# Sheet1.net
KiCad netlist of a schematic drawn in Altium Designer
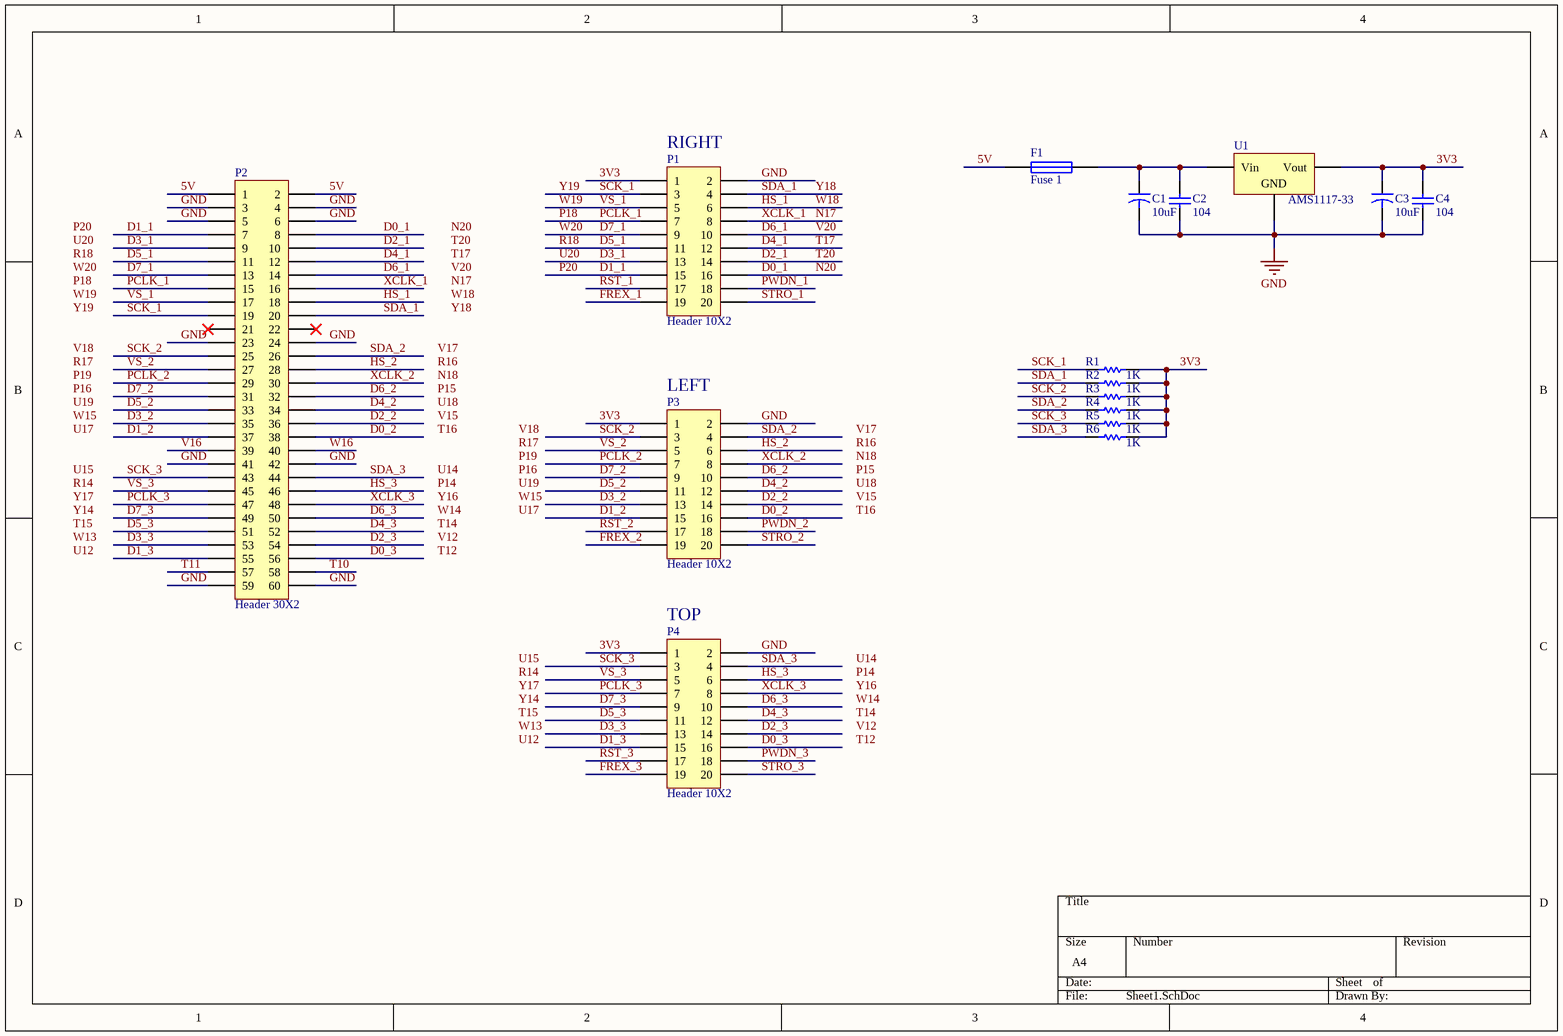
[diagram p0: Sheet1.SchDoc]

(export (version "E")
  (design (tool "Eeschema 10.0.6"))
  (components
    (comp (ref "C1")
      (value "10uF")
      (footprint "R0805")
      (description "Capacitor")
      (fields (field (name "Comment") "Cap2") (field (name "PUBLISHER") "Altium Limited"))
      (libsource (lib "Miscellaneous Devices") (part "Cap2"))
    )
    (comp (ref "C2")
      (value "104")
      (footprint "R0805")
      (description "Capacitor")
      (fields (field (name "Comment") "Cap") (field (name "PUBLISHER") "Altium Limited"))
      (libsource (lib "Miscellaneous Devices") (part "Cap"))
    )
    (comp (ref "C3")
      (value "10uF")
      (footprint "R0805")
      (description "Capacitor")
      (fields (field (name "Comment") "Cap2") (field (name "PUBLISHER") "Altium Limited"))
      (libsource (lib "Miscellaneous Devices") (part "Cap2"))
    )
    (comp (ref "C4")
      (value "104")
      (footprint "R0805")
      (description "Capacitor")
      (fields (field (name "Comment") "Cap") (field (name "PUBLISHER") "Altium Limited"))
      (libsource (lib "Miscellaneous Devices") (part "Cap"))
    )
    (comp (ref "F1")
      (value "Fuse 1")
      (footprint "R1206")
      (description "Fuse")
      (fields (field (name "PUBLISHER") "Altium Limited"))
      (libsource (lib "Miscellaneous Devices") (part "Fuse 1"))
    )
    (comp (ref "P1")
      (value "Header 10X2")
      (footprint "PCBComponent_1")
      (description "Header, 10-Pin, Dual row")
      (fields (field (name "PUBLISHER") "Altium Limited"))
      (libsource (lib "Miscellaneous Connectors") (part "Header 10X2"))
    )
    (comp (ref "P2")
      (value "Header 30X2")
      (footprint "BTBCON_0.8mm_60P")
      (description "Header, 30-Pin, Dual row")
      (fields (field (name "PUBLISHER") "Altium Limited"))
      (libsource (lib "Miscellaneous Connectors") (part "Header 30X2"))
    )
    (comp (ref "P3")
      (value "Header 10X2")
      (footprint "PCBComponent_1")
      (description "Header, 10-Pin, Dual row")
      (fields (field (name "PUBLISHER") "Altium Limited"))
      (libsource (lib "Miscellaneous Connectors") (part "Header 10X2"))
    )
    (comp (ref "P4")
      (value "Header 10X2")
      (footprint "PCBComponent_1")
      (description "Header, 10-Pin, Dual row")
      (fields (field (name "PUBLISHER") "Altium Limited"))
      (libsource (lib "Miscellaneous Connectors") (part "Header 10X2"))
    )
    (comp (ref "R1")
      (value "1K")
      (footprint "R0805")
      (description "Resistor")
      (fields (field (name "Comment") "Res1") (field (name "PUBLISHER") "Altium Limited"))
      (libsource (lib "Miscellaneous Devices") (part "Res1"))
    )
    (comp (ref "R2")
      (value "1K")
      (footprint "R0805")
      (description "Resistor")
      (fields (field (name "Comment") "Res1") (field (name "PUBLISHER") "Altium Limited"))
      (libsource (lib "Miscellaneous Devices") (part "Res1"))
    )
    (comp (ref "R3")
      (value "1K")
      (footprint "R0805")
      (description "Resistor")
      (fields (field (name "Comment") "Res1") (field (name "PUBLISHER") "Altium Limited"))
      (libsource (lib "Miscellaneous Devices") (part "Res1"))
    )
    (comp (ref "R4")
      (value "1K")
      (footprint "R0805")
      (description "Resistor")
      (fields (field (name "Comment") "Res1") (field (name "PUBLISHER") "Altium Limited"))
      (libsource (lib "Miscellaneous Devices") (part "Res1"))
    )
    (comp (ref "R5")
      (value "1K")
      (footprint "R0805")
      (description "Resistor")
      (fields (field (name "Comment") "Res1") (field (name "PUBLISHER") "Altium Limited"))
      (libsource (lib "Miscellaneous Devices") (part "Res1"))
    )
    (comp (ref "R6")
      (value "1K")
      (footprint "R0805")
      (description "Resistor")
      (fields (field (name "Comment") "Res1") (field (name "PUBLISHER") "Altium Limited"))
      (libsource (lib "Miscellaneous Devices") (part "Res1"))
    )
    (comp (ref "U1")
      (value "AMS1117-33")
      (footprint "SOT-223   AMS1117")
      (description "Voltage Regulator")
      (fields (field (name "PUBLISHER") "Altium Limited"))
      (libsource (lib "Miscellaneous Devices") (part "Volt Reg"))
    )
  )
  (nets
    (net (code "1") (name "/3V3") (class "Default")
      (node (ref "C3") (pin "1") (pinfunction "1_1") (pintype "passive"))
      (node (ref "C4") (pin "2") (pinfunction "2_2") (pintype "passive"))
      (node (ref "P1") (pin "1") (pinfunction "1_1") (pintype "passive"))
      (node (ref "P3") (pin "1") (pinfunction "1_1") (pintype "passive"))
      (node (ref "P4") (pin "1") (pinfunction "1_1") (pintype "passive"))
      (node (ref "R1") (pin "1") (pinfunction "1_1") (pintype "passive"))
      (node (ref "R2") (pin "1") (pinfunction "1_1") (pintype "passive"))
      (node (ref "R3") (pin "1") (pinfunction "1_1") (pintype "passive"))
      (node (ref "R4") (pin "1") (pinfunction "1_1") (pintype "passive"))
      (node (ref "R5") (pin "1") (pinfunction "1_1") (pintype "passive"))
      (node (ref "R6") (pin "1") (pinfunction "1_1") (pintype "passive"))
      (node (ref "U1") (pin "2") (pinfunction "Vout_2") (pintype "passive"))
    )
    (net (code "2") (name "/5V") (class "Default")
      (node (ref "F1") (pin "1") (pinfunction "1_1") (pintype "passive"))
      (node (ref "P2") (pin "1") (pinfunction "1_1") (pintype "passive"))
      (node (ref "P2") (pin "2") (pinfunction "2_2") (pintype "passive"))
    )
    (net (code "3") (name "/D0_1") (class "Default")
      (node (ref "P1") (pin "16") (pinfunction "16_16") (pintype "passive"))
      (node (ref "P2") (pin "8") (pinfunction "8_8") (pintype "passive"))
    )
    (net (code "4") (name "/D0_2") (class "Default")
      (node (ref "P2") (pin "38") (pinfunction "38_38") (pintype "passive"))
      (node (ref "P3") (pin "16") (pinfunction "16_16") (pintype "passive"))
    )
    (net (code "5") (name "/D0_3") (class "Default")
      (node (ref "P2") (pin "56") (pinfunction "56_56") (pintype "passive"))
      (node (ref "P4") (pin "16") (pinfunction "16_16") (pintype "passive"))
    )
    (net (code "6") (name "/D1_1") (class "Default")
      (node (ref "P1") (pin "15") (pinfunction "15_15") (pintype "passive"))
      (node (ref "P2") (pin "7") (pinfunction "7_7") (pintype "passive"))
    )
    (net (code "7") (name "/D1_2") (class "Default")
      (node (ref "P2") (pin "37") (pinfunction "37_37") (pintype "passive"))
      (node (ref "P3") (pin "15") (pinfunction "15_15") (pintype "passive"))
    )
    (net (code "8") (name "/D1_3") (class "Default")
      (node (ref "P2") (pin "55") (pinfunction "55_55") (pintype "passive"))
      (node (ref "P4") (pin "15") (pinfunction "15_15") (pintype "passive"))
    )
    (net (code "9") (name "/D2_1") (class "Default")
      (node (ref "P1") (pin "14") (pinfunction "14_14") (pintype "passive"))
      (node (ref "P2") (pin "10") (pinfunction "10_10") (pintype "passive"))
    )
    (net (code "10") (name "/D2_2") (class "Default")
      (node (ref "P2") (pin "36") (pinfunction "36_36") (pintype "passive"))
      (node (ref "P3") (pin "14") (pinfunction "14_14") (pintype "passive"))
    )
    (net (code "11") (name "/D2_3") (class "Default")
      (node (ref "P2") (pin "54") (pinfunction "54_54") (pintype "passive"))
      (node (ref "P4") (pin "14") (pinfunction "14_14") (pintype "passive"))
    )
    (net (code "12") (name "/D3_1") (class "Default")
      (node (ref "P1") (pin "13") (pinfunction "13_13") (pintype "passive"))
      (node (ref "P2") (pin "9") (pinfunction "9_9") (pintype "passive"))
    )
    (net (code "13") (name "/D3_2") (class "Default")
      (node (ref "P2") (pin "35") (pinfunction "35_35") (pintype "passive"))
      (node (ref "P3") (pin "13") (pinfunction "13_13") (pintype "passive"))
    )
    (net (code "14") (name "/D3_3") (class "Default")
      (node (ref "P2") (pin "53") (pinfunction "53_53") (pintype "passive"))
      (node (ref "P4") (pin "13") (pinfunction "13_13") (pintype "passive"))
    )
    (net (code "15") (name "/D4_1") (class "Default")
      (node (ref "P1") (pin "12") (pinfunction "12_12") (pintype "passive"))
      (node (ref "P2") (pin "12") (pinfunction "12_12") (pintype "passive"))
    )
    (net (code "16") (name "/D4_2") (class "Default")
      (node (ref "P2") (pin "34") (pinfunction "34_34") (pintype "passive"))
      (node (ref "P3") (pin "12") (pinfunction "12_12") (pintype "passive"))
    )
    (net (code "17") (name "/D4_3") (class "Default")
      (node (ref "P2") (pin "52") (pinfunction "52_52") (pintype "passive"))
      (node (ref "P4") (pin "12") (pinfunction "12_12") (pintype "passive"))
    )
    (net (code "18") (name "/D5_1") (class "Default")
      (node (ref "P1") (pin "11") (pinfunction "11_11") (pintype "passive"))
      (node (ref "P2") (pin "11") (pinfunction "11_11") (pintype "passive"))
    )
    (net (code "19") (name "/D5_2") (class "Default")
      (node (ref "P2") (pin "33") (pinfunction "33_33") (pintype "passive"))
      (node (ref "P3") (pin "11") (pinfunction "11_11") (pintype "passive"))
    )
    (net (code "20") (name "/D5_3") (class "Default")
      (node (ref "P2") (pin "51") (pinfunction "51_51") (pintype "passive"))
      (node (ref "P4") (pin "11") (pinfunction "11_11") (pintype "passive"))
    )
    (net (code "21") (name "/D6_1") (class "Default")
      (node (ref "P1") (pin "10") (pinfunction "10_10") (pintype "passive"))
      (node (ref "P2") (pin "14") (pinfunction "14_14") (pintype "passive"))
    )
    (net (code "22") (name "/D6_2") (class "Default")
      (node (ref "P2") (pin "32") (pinfunction "32_32") (pintype "passive"))
      (node (ref "P3") (pin "10") (pinfunction "10_10") (pintype "passive"))
    )
    (net (code "23") (name "/D6_3") (class "Default")
      (node (ref "P2") (pin "50") (pinfunction "50_50") (pintype "passive"))
      (node (ref "P4") (pin "10") (pinfunction "10_10") (pintype "passive"))
    )
    (net (code "24") (name "/D7_1") (class "Default")
      (node (ref "P1") (pin "9") (pinfunction "9_9") (pintype "passive"))
      (node (ref "P2") (pin "13") (pinfunction "13_13") (pintype "passive"))
    )
    (net (code "25") (name "/D7_2") (class "Default")
      (node (ref "P2") (pin "31") (pinfunction "31_31") (pintype "passive"))
      (node (ref "P3") (pin "9") (pinfunction "9_9") (pintype "passive"))
    )
    (net (code "26") (name "/D7_3") (class "Default")
      (node (ref "P2") (pin "49") (pinfunction "49_49") (pintype "passive"))
      (node (ref "P4") (pin "9") (pinfunction "9_9") (pintype "passive"))
    )
    (net (code "27") (name "/FREX_1") (class "Default")
      (node (ref "P1") (pin "19") (pinfunction "19_19") (pintype "passive"))
    )
    (net (code "28") (name "/FREX_2") (class "Default")
      (node (ref "P3") (pin "19") (pinfunction "19_19") (pintype "passive"))
    )
    (net (code "29") (name "/FREX_3") (class "Default")
      (node (ref "P4") (pin "19") (pinfunction "19_19") (pintype "passive"))
    )
    (net (code "30") (name "/HS_1") (class "Default")
      (node (ref "P1") (pin "6") (pinfunction "6_6") (pintype "passive"))
      (node (ref "P2") (pin "18") (pinfunction "18_18") (pintype "passive"))
    )
    (net (code "31") (name "/HS_2") (class "Default")
      (node (ref "P2") (pin "28") (pinfunction "28_28") (pintype "passive"))
      (node (ref "P3") (pin "6") (pinfunction "6_6") (pintype "passive"))
    )
    (net (code "32") (name "/HS_3") (class "Default")
      (node (ref "P2") (pin "46") (pinfunction "46_46") (pintype "passive"))
      (node (ref "P4") (pin "6") (pinfunction "6_6") (pintype "passive"))
    )
    (net (code "33") (name "/N17") (class "Default")
      (node (ref "P1") (pin "8") (pinfunction "8_8") (pintype "passive"))
      (node (ref "P2") (pin "16") (pinfunction "16_16") (pintype "passive"))
    )
    (net (code "38") (name "/P18") (class "Default")
      (node (ref "P1") (pin "7") (pinfunction "7_7") (pintype "passive"))
      (node (ref "P2") (pin "15") (pinfunction "15_15") (pintype "passive"))
    )
    (net (code "40") (name "/PCLK_2") (class "Default")
      (node (ref "P2") (pin "29") (pinfunction "29_29") (pintype "passive"))
      (node (ref "P3") (pin "7") (pinfunction "7_7") (pintype "passive"))
    )
    (net (code "41") (name "/PCLK_3") (class "Default")
      (node (ref "P2") (pin "47") (pinfunction "47_47") (pintype "passive"))
      (node (ref "P4") (pin "7") (pinfunction "7_7") (pintype "passive"))
    )
    (net (code "42") (name "/PWDN_1") (class "Default")
      (node (ref "P1") (pin "18") (pinfunction "18_18") (pintype "passive"))
    )
    (net (code "43") (name "/PWDN_2") (class "Default")
      (node (ref "P3") (pin "18") (pinfunction "18_18") (pintype "passive"))
    )
    (net (code "44") (name "/PWDN_3") (class "Default")
      (node (ref "P4") (pin "18") (pinfunction "18_18") (pintype "passive"))
    )
    (net (code "48") (name "/RST_1") (class "Default")
      (node (ref "P1") (pin "17") (pinfunction "17_17") (pintype "passive"))
    )
    (net (code "49") (name "/RST_2") (class "Default")
      (node (ref "P3") (pin "17") (pinfunction "17_17") (pintype "passive"))
    )
    (net (code "50") (name "/RST_3") (class "Default")
      (node (ref "P4") (pin "17") (pinfunction "17_17") (pintype "passive"))
    )
    (net (code "51") (name "/SCK_1") (class "Default")
      (node (ref "P1") (pin "3") (pinfunction "3_3") (pintype "passive"))
      (node (ref "P2") (pin "19") (pinfunction "19_19") (pintype "passive"))
      (node (ref "R1") (pin "2") (pinfunction "2_2") (pintype "passive"))
    )
    (net (code "52") (name "/SCK_2") (class "Default")
      (node (ref "P2") (pin "25") (pinfunction "25_25") (pintype "passive"))
      (node (ref "P3") (pin "3") (pinfunction "3_3") (pintype "passive"))
      (node (ref "R3") (pin "2") (pinfunction "2_2") (pintype "passive"))
    )
    (net (code "53") (name "/SCK_3") (class "Default")
      (node (ref "P2") (pin "43") (pinfunction "43_43") (pintype "passive"))
      (node (ref "P4") (pin "3") (pinfunction "3_3") (pintype "passive"))
      (node (ref "R5") (pin "2") (pinfunction "2_2") (pintype "passive"))
    )
    (net (code "54") (name "/SDA_1") (class "Default")
      (node (ref "P1") (pin "4") (pinfunction "4_4") (pintype "passive"))
      (node (ref "P2") (pin "20") (pinfunction "20_20") (pintype "passive"))
      (node (ref "R2") (pin "2") (pinfunction "2_2") (pintype "passive"))
    )
    (net (code "55") (name "/SDA_2") (class "Default")
      (node (ref "P2") (pin "26") (pinfunction "26_26") (pintype "passive"))
      (node (ref "P3") (pin "4") (pinfunction "4_4") (pintype "passive"))
      (node (ref "R4") (pin "2") (pinfunction "2_2") (pintype "passive"))
    )
    (net (code "56") (name "/SDA_3") (class "Default")
      (node (ref "P2") (pin "44") (pinfunction "44_44") (pintype "passive"))
      (node (ref "P4") (pin "4") (pinfunction "4_4") (pintype "passive"))
      (node (ref "R6") (pin "2") (pinfunction "2_2") (pintype "passive"))
    )
    (net (code "57") (name "/STRO_1") (class "Default")
      (node (ref "P1") (pin "20") (pinfunction "20_20") (pintype "passive"))
    )
    (net (code "58") (name "/STRO_2") (class "Default")
      (node (ref "P3") (pin "20") (pinfunction "20_20") (pintype "passive"))
    )
    (net (code "59") (name "/STRO_3") (class "Default")
      (node (ref "P4") (pin "20") (pinfunction "20_20") (pintype "passive"))
    )
    (net (code "60") (name "/T10") (class "Default")
      (node (ref "P2") (pin "58") (pinfunction "58_58") (pintype "passive"))
    )
    (net (code "61") (name "/T11") (class "Default")
      (node (ref "P2") (pin "57") (pinfunction "57_57") (pintype "passive"))
    )
    (net (code "74") (name "/V16") (class "Default")
      (node (ref "P2") (pin "39") (pinfunction "39_39") (pintype "passive"))
    )
    (net (code "77") (name "/VS_1") (class "Default")
      (node (ref "P1") (pin "5") (pinfunction "5_5") (pintype "passive"))
      (node (ref "P2") (pin "17") (pinfunction "17_17") (pintype "passive"))
    )
    (net (code "78") (name "/VS_2") (class "Default")
      (node (ref "P2") (pin "27") (pinfunction "27_27") (pintype "passive"))
      (node (ref "P3") (pin "5") (pinfunction "5_5") (pintype "passive"))
    )
    (net (code "79") (name "/VS_3") (class "Default")
      (node (ref "P2") (pin "45") (pinfunction "45_45") (pintype "passive"))
      (node (ref "P4") (pin "5") (pinfunction "5_5") (pintype "passive"))
    )
    (net (code "83") (name "/W16") (class "Default")
      (node (ref "P2") (pin "40") (pinfunction "40_40") (pintype "passive"))
    )
    (net (code "84") (name "/XCLK_2") (class "Default")
      (node (ref "P2") (pin "30") (pinfunction "30_30") (pintype "passive"))
      (node (ref "P3") (pin "8") (pinfunction "8_8") (pintype "passive"))
    )
    (net (code "85") (name "/XCLK_3") (class "Default")
      (node (ref "P2") (pin "48") (pinfunction "48_48") (pintype "passive"))
      (node (ref "P4") (pin "8") (pinfunction "8_8") (pintype "passive"))
    )
    (net (code "89") (name "GND") (class "Default")
      (node (ref "C1") (pin "2") (pinfunction "2_2") (pintype "passive"))
      (node (ref "C2") (pin "1") (pinfunction "1_1") (pintype "passive"))
      (node (ref "C3") (pin "2") (pinfunction "2_2") (pintype "passive"))
      (node (ref "C4") (pin "1") (pinfunction "1_1") (pintype "passive"))
      (node (ref "P1") (pin "2") (pinfunction "2_2") (pintype "passive"))
      (node (ref "P2") (pin "23") (pinfunction "23_23") (pintype "passive"))
      (node (ref "P2") (pin "24") (pinfunction "24_24") (pintype "passive"))
      (node (ref "P2") (pin "3") (pinfunction "3_3") (pintype "passive"))
      (node (ref "P2") (pin "4") (pinfunction "4_4") (pintype "passive"))
      (node (ref "P2") (pin "41") (pinfunction "41_41") (pintype "passive"))
      (node (ref "P2") (pin "42") (pinfunction "42_42") (pintype "passive"))
      (node (ref "P2") (pin "5") (pinfunction "5_5") (pintype "passive"))
      (node (ref "P2") (pin "59") (pinfunction "59_59") (pintype "passive"))
      (node (ref "P2") (pin "6") (pinfunction "6_6") (pintype "passive"))
      (node (ref "P2") (pin "60") (pinfunction "60_60") (pintype "passive"))
      (node (ref "P3") (pin "2") (pinfunction "2_2") (pintype "passive"))
      (node (ref "P4") (pin "2") (pinfunction "2_2") (pintype "passive"))
      (node (ref "U1") (pin "1") (pinfunction "GND_1") (pintype "passive"))
    )
    (net (code "90") (name "Net-(U1-Vin)") (class "Default")
      (node (ref "C1") (pin "1") (pinfunction "1_1") (pintype "passive"))
      (node (ref "C2") (pin "2") (pinfunction "2_2") (pintype "passive"))
      (node (ref "F1") (pin "2") (pinfunction "2_2") (pintype "passive"))
      (node (ref "U1") (pin "3") (pinfunction "Vin_3") (pintype "passive"))
    )
    (net (code "91") (name "unconnected-(P2-Pad21)") (class "Default")
      (node (ref "P2") (pin "21") (pinfunction "21_21") (pintype "passive+no_connect"))
    )
    (net (code "92") (name "unconnected-(P2-Pad22)") (class "Default")
      (node (ref "P2") (pin "22") (pinfunction "22_22") (pintype "passive+no_connect"))
    )
  )
)
